# ECU_Dummy.net
KiCad netlist of a schematic drawn in Altium Designer
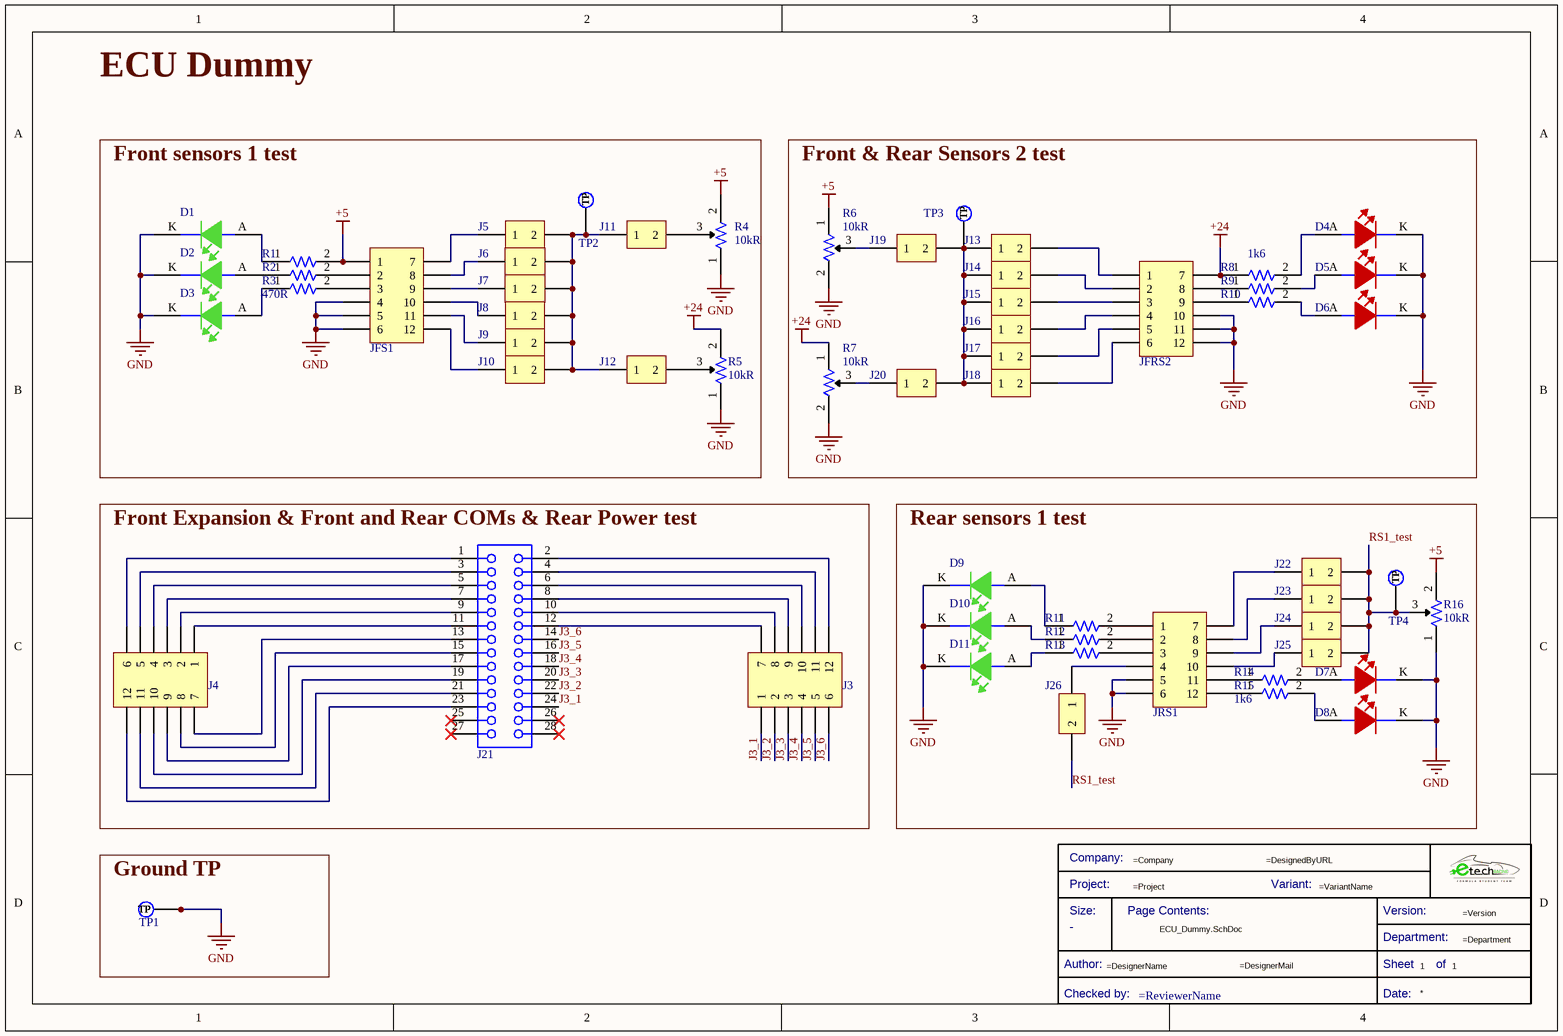
[diagram p0: ECU_Dummy.SchDoc]

(export (version "E")
  (design (tool "Eeschema 10.0.6"))
  (components
    (comp (ref "*")
      (value "Title Block_template")
      (description "Standard Title Block")
      (fields
        (field (name "SIZE") "-")
        (field (name ".CREATOR") "GP")
        (field (name ".PCBCHECK") "GP")
        (field (name ".SCHCHECK") "GP")
      )
      (libsource (lib "e-Tech_Racing") (part "Title Block_template"))
    )
    (comp (ref "D1")
      (value "150080GS75000")
      (footprint "LED_0805_WE")
      (description "Led, Green, 520 Nm, 3.2 V, 30 Ma, 450 Mcd Rohs Compliant: Yes")
      (fields (field (name ".CREATOR") "GP"))
      (libsource (lib "Semiconductor") (part "LEDGS-0805-450"))
    )
    (comp (ref "D2")
      (value "150080GS75000")
      (footprint "LED_0805_WE")
      (description "Led, Green, 520 Nm, 3.2 V, 30 Ma, 450 Mcd Rohs Compliant: Yes")
      (fields (field (name ".CREATOR") "GP"))
      (libsource (lib "Semiconductor") (part "LEDGS-0805-450"))
    )
    (comp (ref "D3")
      (value "150080GS75000")
      (footprint "LED_0805_WE")
      (description "Led, Green, 520 Nm, 3.2 V, 30 Ma, 450 Mcd Rohs Compliant: Yes")
      (fields (field (name ".CREATOR") "GP"))
      (libsource (lib "Semiconductor") (part "LEDGS-0805-450"))
    )
    (comp (ref "D4")
      (value "150080RS75000")
      (footprint "LED_0805_WE")
      (description "0805(H=0.8mm) 红色 高亮 λD=625nm VF=2V IF=30mA PD=72mW")
      (fields (field (name ".CREATOR") "DR"))
      (libsource (lib "Semiconductor") (part "LEDRS-0805-150"))
    )
    (comp (ref "D5")
      (value "150080RS75000")
      (footprint "LED_0805_WE")
      (description "0805(H=0.8mm) 红色 高亮 λD=625nm VF=2V IF=30mA PD=72mW")
      (fields (field (name ".CREATOR") "DR"))
      (libsource (lib "Semiconductor") (part "LEDRS-0805-150"))
    )
    (comp (ref "D6")
      (value "150080RS75000")
      (footprint "LED_0805_WE")
      (description "0805(H=0.8mm) 红色 高亮 λD=625nm VF=2V IF=30mA PD=72mW")
      (fields (field (name ".CREATOR") "DR"))
      (libsource (lib "Semiconductor") (part "LEDRS-0805-150"))
    )
    (comp (ref "D7")
      (value "150080RS75000")
      (footprint "LED_0805_WE")
      (description "0805(H=0.8mm) 红色 高亮 λD=625nm VF=2V IF=30mA PD=72mW")
      (fields (field (name ".CREATOR") "DR"))
      (libsource (lib "Semiconductor") (part "LEDRS-0805-150"))
    )
    (comp (ref "D8")
      (value "150080RS75000")
      (footprint "LED_0805_WE")
      (description "0805(H=0.8mm) 红色 高亮 λD=625nm VF=2V IF=30mA PD=72mW")
      (fields (field (name ".CREATOR") "DR"))
      (libsource (lib "Semiconductor") (part "LEDRS-0805-150"))
    )
    (comp (ref "D9")
      (value "150080GS75000")
      (footprint "LED_0805_WE")
      (description "Led, Green, 520 Nm, 3.2 V, 30 Ma, 450 Mcd Rohs Compliant: Yes")
      (fields (field (name ".CREATOR") "GP"))
      (libsource (lib "Semiconductor") (part "LEDGS-0805-450"))
    )
    (comp (ref "D10")
      (value "150080GS75000")
      (footprint "LED_0805_WE")
      (description "Led, Green, 520 Nm, 3.2 V, 30 Ma, 450 Mcd Rohs Compliant: Yes")
      (fields (field (name ".CREATOR") "GP"))
      (libsource (lib "Semiconductor") (part "LEDGS-0805-450"))
    )
    (comp (ref "D11")
      (value "150080GS75000")
      (footprint "LED_0805_WE")
      (description "Led, Green, 520 Nm, 3.2 V, 30 Ma, 450 Mcd Rohs Compliant: Yes")
      (fields (field (name ".CREATOR") "GP"))
      (libsource (lib "Semiconductor") (part "LEDGS-0805-450"))
    )
    (comp (ref "J3")
      (value "1053101112")
      (footprint "J_NanoFit_2x6_V")
      (libsource (lib "Electromechanical") (part "J_NanoFit_2x6_V"))
    )
    (comp (ref "J4")
      (value "1053101112")
      (footprint "J_NanoFit_2x6_V")
      (libsource (lib "") (part "J_NanoFit_2x6_V_1"))
    )
    (comp (ref "J5")
      (value "2 Pin Header")
      (footprint "J_Pinheader_1x2")
      (libsource (lib "Electromechanical") (part "J_Jumper_H"))
    )
    (comp (ref "J6")
      (value "2 Pin Header")
      (footprint "J_Pinheader_1x2")
      (libsource (lib "") (part "J_Jumper_H_2"))
    )
    (comp (ref "J7")
      (value "2 Pin Header")
      (footprint "J_Pinheader_1x2")
      (libsource (lib "") (part "J_Jumper_H_2"))
    )
    (comp (ref "J8")
      (value "2 Pin Header")
      (footprint "J_Pinheader_1x2")
      (libsource (lib "Electromechanical") (part "J_Jumper_H"))
    )
    (comp (ref "J9")
      (value "2 Pin Header")
      (footprint "J_Pinheader_1x2")
      (libsource (lib "Electromechanical") (part "J_Jumper_H"))
    )
    (comp (ref "J10")
      (value "2 Pin Header")
      (footprint "J_Pinheader_1x2")
      (libsource (lib "Electromechanical") (part "J_Jumper_H"))
    )
    (comp (ref "J11")
      (value "2 Pin Header")
      (footprint "J_Pinheader_1x2")
      (libsource (lib "Electromechanical") (part "J_Jumper_H"))
    )
    (comp (ref "J12")
      (value "2 Pin Header")
      (footprint "J_Pinheader_1x2")
      (libsource (lib "Electromechanical") (part "J_Jumper_H"))
    )
    (comp (ref "J13")
      (value "2 Pin Header")
      (footprint "J_Pinheader_1x2")
      (libsource (lib "Electromechanical") (part "J_Jumper_H"))
    )
    (comp (ref "J14")
      (value "2 Pin Header")
      (footprint "J_Pinheader_1x2")
      (libsource (lib "Electromechanical") (part "J_Jumper_H"))
    )
    (comp (ref "J15")
      (value "2 Pin Header")
      (footprint "J_Pinheader_1x2")
      (libsource (lib "Electromechanical") (part "J_Jumper_H"))
    )
    (comp (ref "J16")
      (value "2 Pin Header")
      (footprint "J_Pinheader_1x2")
      (libsource (lib "Electromechanical") (part "J_Jumper_H"))
    )
    (comp (ref "J17")
      (value "2 Pin Header")
      (footprint "J_Pinheader_1x2")
      (libsource (lib "Electromechanical") (part "J_Jumper_H"))
    )
    (comp (ref "J18")
      (value "2 Pin Header")
      (footprint "J_Pinheader_1x2")
      (libsource (lib "Electromechanical") (part "J_Jumper_H"))
    )
    (comp (ref "J19")
      (value "2 Pin Header")
      (footprint "J_Pinheader_1x2")
      (libsource (lib "Electromechanical") (part "J_Jumper_H"))
    )
    (comp (ref "J20")
      (value "2 Pin Header")
      (footprint "J_Pinheader_1x2")
      (libsource (lib "Electromechanical") (part "J_Jumper_H"))
    )
    (comp (ref "J21")
      (value "61002821821")
      (footprint "61002821821")
      (description "WR-PHD Socket Header, SMT, Vertical, pitch 2.54mm, 2 Row, 28P")
      (fields (field (name "MANUFACTURER") "Wurth Elektronik"))
      (libsource (lib "Electromechanical") (part "61002821821"))
    )
    (comp (ref "J22")
      (value "2 Pin Header")
      (footprint "J_Pinheader_1x2")
      (libsource (lib "Electromechanical") (part "J_Jumper_H"))
    )
    (comp (ref "J23")
      (value "2 Pin Header")
      (footprint "J_Pinheader_1x2")
      (libsource (lib "Electromechanical") (part "J_Jumper_H"))
    )
    (comp (ref "J24")
      (value "2 Pin Header")
      (footprint "J_Pinheader_1x2")
      (libsource (lib "Electromechanical") (part "J_Jumper_H"))
    )
    (comp (ref "J25")
      (value "2 Pin Header")
      (footprint "J_Pinheader_1x2")
      (libsource (lib "Electromechanical") (part "J_Jumper_H"))
    )
    (comp (ref "J26")
      (value "2 Pin Header")
      (footprint "J_Pinheader_1x2")
      (libsource (lib "") (part "J_Jumper_H_1"))
    )
    (comp (ref "JFRS2")
      (value "1053101112")
      (footprint "J_NanoFit_2x6_V")
      (libsource (lib "") (part "J_NanoFit_2x6_V_2"))
    )
    (comp (ref "JFS1")
      (value "1053101112")
      (footprint "J_NanoFit_2x6_V")
      (libsource (lib "") (part "J_NanoFit_2x6_V_2"))
    )
    (comp (ref "JRS1")
      (value "1053101112")
      (footprint "J_NanoFit_2x6_V")
      (libsource (lib "") (part "J_NanoFit_2x6_V_2"))
    )
    (comp (ref "R1")
      (value "CR0805-FX-4700GLF")
      (footprint "R0805FTK")
      (description "Res Thick Film 0805 470 Ohm 1% 1/8W ±100ppm/°C Molded SMD SMD Paper Tape on Plastic Reel")
      (fields (field (name "TOLERANCE") "1%") (field (name ".CREATOR") "DR"))
      (libsource (lib "Passives") (part "R470-0805FTK"))
    )
    (comp (ref "R2")
      (value "CR0805-FX-4700GLF")
      (footprint "R0805FTK")
      (description "Res Thick Film 0805 470 Ohm 1% 1/8W ±100ppm/°C Molded SMD SMD Paper Tape on Plastic Reel")
      (fields (field (name "TOLERANCE") "1%") (field (name ".CREATOR") "DR"))
      (libsource (lib "Passives") (part "R470-0805FTK"))
    )
    (comp (ref "R3")
      (value "CR0805-FX-4700GLF")
      (footprint "R0805FTK")
      (description "Res Thick Film 0805 470 Ohm 1% 1/8W ±100ppm/°C Molded SMD SMD Paper Tape on Plastic Reel")
      (fields (field (name "TOLERANCE") "1%") (field (name ".CREATOR") "DR"))
      (libsource (lib "Passives") (part "R470-0805FTK"))
    )
    (comp (ref "R4")
      (value "3296W-1-103LF")
      (footprint "R10k-VTR")
      (description "Trimmer, Cermet, Rest 10 Kilohms, PCB, 25 Turns, Pwr-Rtg 0.5W, 3296 Series")
      (fields
        (field (name "MANUFACTURER") "Bourns")
        (field (name "TOLERANCE") "10%")
        (field (name "RESISTANCE") "10kR")
        (field (name ".CREATOR") "DO")
      )
      (libsource (lib "Passives") (part "R10k-VTR"))
    )
    (comp (ref "R5")
      (value "3296W-1-103LF")
      (footprint "R10k-VTR")
      (description "Trimmer, Cermet, Rest 10 Kilohms, PCB, 25 Turns, Pwr-Rtg 0.5W, 3296 Series")
      (fields
        (field (name "MANUFACTURER") "Bourns")
        (field (name "TOLERANCE") "10%")
        (field (name "RESISTANCE") "10kR")
        (field (name ".CREATOR") "DO")
      )
      (libsource (lib "Passives") (part "R10k-VTR"))
    )
    (comp (ref "R6")
      (value "3296W-1-103LF")
      (footprint "R10k-VTR")
      (description "Trimmer, Cermet, Rest 10 Kilohms, PCB, 25 Turns, Pwr-Rtg 0.5W, 3296 Series")
      (fields
        (field (name "MANUFACTURER") "Bourns")
        (field (name "TOLERANCE") "10%")
        (field (name "RESISTANCE") "10kR")
        (field (name ".CREATOR") "DO")
      )
      (libsource (lib "Passives") (part "R10k-VTR"))
    )
    (comp (ref "R7")
      (value "3296W-1-103LF")
      (footprint "R10k-VTR")
      (description "Trimmer, Cermet, Rest 10 Kilohms, PCB, 25 Turns, Pwr-Rtg 0.5W, 3296 Series")
      (fields
        (field (name "MANUFACTURER") "Bourns")
        (field (name "TOLERANCE") "10%")
        (field (name "RESISTANCE") "10kR")
        (field (name ".CREATOR") "DO")
      )
      (libsource (lib "Passives") (part "R10k-VTR"))
    )
    (comp (ref "R8")
      (value "CR1206-FX-2201ELF")
      (footprint "R1206FTK-W")
      (description "Res Thick Film 1206 2.2K Ohm 1% 1/4W ±100ppm/°C Molded SMD SMD Paper Tape on Plastic Reel")
      (fields (field (name "TOLERANCE") "1%") (field (name ".CREATOR") "AC"))
      (libsource (lib "Passives") (part "R2.2K-1206FTK"))
    )
    (comp (ref "R9")
      (value "CR1206-FX-2201ELF")
      (footprint "R1206FTK-W")
      (description "Res Thick Film 1206 2.2K Ohm 1% 1/4W ±100ppm/°C Molded SMD SMD Paper Tape on Plastic Reel")
      (fields (field (name "TOLERANCE") "1%") (field (name ".CREATOR") "AC"))
      (libsource (lib "Passives") (part "R2.2K-1206FTK"))
    )
    (comp (ref "R10")
      (value "CR1206-FX-2201ELF")
      (footprint "R1206FTK-W")
      (description "Res Thick Film 1206 2.2K Ohm 1% 1/4W ±100ppm/°C Molded SMD SMD Paper Tape on Plastic Reel")
      (fields (field (name "TOLERANCE") "1%") (field (name ".CREATOR") "AC"))
      (libsource (lib "Passives") (part "R2.2K-1206FTK"))
    )
    (comp (ref "R11")
      (value "CR0805-FX-4700GLF")
      (footprint "R0805FTK")
      (description "Res Thick Film 0805 470 Ohm 1% 1/8W ±100ppm/°C Molded SMD SMD Paper Tape on Plastic Reel")
      (fields (field (name "TOLERANCE") "1%") (field (name ".CREATOR") "DR"))
      (libsource (lib "Passives") (part "R470-0805FTK"))
    )
    (comp (ref "R12")
      (value "CR0805-FX-4700GLF")
      (footprint "R0805FTK")
      (description "Res Thick Film 0805 470 Ohm 1% 1/8W ±100ppm/°C Molded SMD SMD Paper Tape on Plastic Reel")
      (fields (field (name "TOLERANCE") "1%") (field (name ".CREATOR") "DR"))
      (libsource (lib "Passives") (part "R470-0805FTK"))
    )
    (comp (ref "R13")
      (value "CR0805-FX-4700GLF")
      (footprint "R0805FTK")
      (description "Res Thick Film 0805 470 Ohm 1% 1/8W ±100ppm/°C Molded SMD SMD Paper Tape on Plastic Reel")
      (fields (field (name "TOLERANCE") "1%") (field (name ".CREATOR") "DR"))
      (libsource (lib "Passives") (part "R470-0805FTK"))
    )
    (comp (ref "R14")
      (value "CR1206-FX-2201ELF")
      (footprint "R1206FTK-W")
      (description "Res Thick Film 1206 2.2K Ohm 1% 1/4W ±100ppm/°C Molded SMD SMD Paper Tape on Plastic Reel")
      (fields (field (name "TOLERANCE") "1%") (field (name ".CREATOR") "AC"))
      (libsource (lib "Passives") (part "R2.2K-1206FTK"))
    )
    (comp (ref "R15")
      (value "CR1206-FX-2201ELF")
      (footprint "R1206FTK-W")
      (description "Res Thick Film 1206 2.2K Ohm 1% 1/4W ±100ppm/°C Molded SMD SMD Paper Tape on Plastic Reel")
      (fields (field (name "TOLERANCE") "1%") (field (name ".CREATOR") "AC"))
      (libsource (lib "Passives") (part "R2.2K-1206FTK"))
    )
    (comp (ref "R16")
      (value "3296W-1-103LF")
      (footprint "R10k-VTR")
      (description "Trimmer, Cermet, Rest 10 Kilohms, PCB, 25 Turns, Pwr-Rtg 0.5W, 3296 Series")
      (fields
        (field (name "MANUFACTURER") "Bourns")
        (field (name "TOLERANCE") "10%")
        (field (name "RESISTANCE") "10kR")
        (field (name ".CREATOR") "DO")
      )
      (libsource (lib "Passives") (part "R10k-VTR"))
    )
    (comp (ref "TP1")
      (value "Test Point")
      (footprint "TESTPOINT_WIDE")
      (description "TestPoint 5x5mm")
      (libsource (lib "e-Tech_Racing") (part "TestPoint_Wide"))
    )
    (comp (ref "TP2")
      (value "TestPoint")
      (footprint "TestPoint")
      (description "Test Point 1x1 mm")
      (fields (field (name ".CREATOR") "GP") (field (name ".PCBCHECK") "GP") (field (name ".SCHCHECK") "GP"))
      (libsource (lib "e-Tech_Racing") (part "TestPoint"))
    )
    (comp (ref "TP3")
      (value "TestPoint")
      (footprint "TestPoint")
      (description "Test Point 1x1 mm")
      (fields (field (name ".CREATOR") "GP") (field (name ".PCBCHECK") "GP") (field (name ".SCHCHECK") "GP"))
      (libsource (lib "e-Tech_Racing") (part "TestPoint"))
    )
    (comp (ref "TP4")
      (value "TestPoint")
      (footprint "TestPoint")
      (description "Test Point 1x1 mm")
      (fields (field (name ".CREATOR") "GP") (field (name ".PCBCHECK") "GP") (field (name ".SCHCHECK") "GP"))
      (libsource (lib "e-Tech_Racing") (part "TestPoint"))
    )
  )
  (nets
    (net (code "1") (name "+5") (class "Default")
      (node (ref "JFS1") (pin "1") (pinfunction "1_1") (pintype "passive"))
      (node (ref "R1") (pin "2") (pinfunction "2_2") (pintype "passive"))
      (node (ref "R16") (pin "2") (pinfunction "2_2") (pintype "passive"))
      (node (ref "R4") (pin "2") (pinfunction "2_2") (pintype "passive"))
      (node (ref "R6") (pin "1") (pinfunction "2_1") (pintype "passive"))
    )
    (net (code "2") (name "+24") (class "Default")
      (node (ref "JFRS2") (pin "7") (pinfunction "7_7") (pintype "passive"))
      (node (ref "R5") (pin "2") (pinfunction "2_2") (pintype "passive"))
      (node (ref "R7") (pin "1") (pinfunction "2_1") (pintype "passive"))
      (node (ref "R8") (pin "1") (pinfunction "1_1") (pintype "passive"))
    )
    (net (code "3") (name "/J3_1") (class "Default")
      (node (ref "J21") (pin "24") (pinfunction "24_24") (pintype "passive"))
      (node (ref "J3") (pin "1") (pinfunction "1_1") (pintype "passive"))
    )
    (net (code "4") (name "/J3_2") (class "Default")
      (node (ref "J21") (pin "22") (pinfunction "22_22") (pintype "passive"))
      (node (ref "J3") (pin "2") (pinfunction "2_2") (pintype "passive"))
    )
    (net (code "5") (name "/J3_3") (class "Default")
      (node (ref "J21") (pin "20") (pinfunction "20_20") (pintype "passive"))
      (node (ref "J3") (pin "3") (pinfunction "3_3") (pintype "passive"))
    )
    (net (code "6") (name "/J3_4") (class "Default")
      (node (ref "J21") (pin "18") (pinfunction "18_18") (pintype "passive"))
      (node (ref "J3") (pin "4") (pinfunction "4_4") (pintype "passive"))
    )
    (net (code "7") (name "/J3_5") (class "Default")
      (node (ref "J21") (pin "16") (pinfunction "16_16") (pintype "passive"))
      (node (ref "J3") (pin "5") (pinfunction "5_5") (pintype "passive"))
    )
    (net (code "8") (name "/J3_6") (class "Default")
      (node (ref "J21") (pin "14") (pinfunction "14_14") (pintype "passive"))
      (node (ref "J3") (pin "6") (pinfunction "6_6") (pintype "passive"))
    )
    (net (code "9") (name "/RS1_test") (class "Default")
      (node (ref "J22") (pin "2") (pinfunction "2_2") (pintype "passive"))
      (node (ref "J23") (pin "2") (pinfunction "2_2") (pintype "passive"))
      (node (ref "J24") (pin "2") (pinfunction "2_2") (pintype "passive"))
      (node (ref "J25") (pin "2") (pinfunction "2_2") (pintype "passive"))
      (node (ref "J26") (pin "2") (pinfunction "2_2") (pintype "passive"))
      (node (ref "R16") (pin "3") (pinfunction "3_3") (pintype "passive"))
      (node (ref "TP4") (pin "1") (pinfunction "TP_1") (pintype "passive"))
    )
    (net (code "10") (name "GND") (class "Default")
      (node (ref "D1") (pin "K") (pinfunction "K_K") (pintype "passive"))
      (node (ref "D10") (pin "K") (pinfunction "K_K") (pintype "passive"))
      (node (ref "D11") (pin "K") (pinfunction "K_K") (pintype "passive"))
      (node (ref "D2") (pin "K") (pinfunction "K_K") (pintype "passive"))
      (node (ref "D3") (pin "K") (pinfunction "K_K") (pintype "passive"))
      (node (ref "D4") (pin "K") (pinfunction "K_K") (pintype "passive"))
      (node (ref "D5") (pin "K") (pinfunction "K_K") (pintype "passive"))
      (node (ref "D6") (pin "K") (pinfunction "K_K") (pintype "passive"))
      (node (ref "D7") (pin "K") (pinfunction "K_K") (pintype "passive"))
      (node (ref "D8") (pin "K") (pinfunction "K_K") (pintype "passive"))
      (node (ref "D9") (pin "K") (pinfunction "K_K") (pintype "passive"))
      (node (ref "JFRS2") (pin "10") (pinfunction "10_10") (pintype "passive"))
      (node (ref "JFRS2") (pin "11") (pinfunction "11_11") (pintype "passive"))
      (node (ref "JFRS2") (pin "12") (pinfunction "12_12") (pintype "passive"))
      (node (ref "JFS1") (pin "4") (pinfunction "4_4") (pintype "passive"))
      (node (ref "JFS1") (pin "5") (pinfunction "5_5") (pintype "passive"))
      (node (ref "JFS1") (pin "6") (pinfunction "6_6") (pintype "passive"))
      (node (ref "JRS1") (pin "5") (pinfunction "5_5") (pintype "passive"))
      (node (ref "JRS1") (pin "6") (pinfunction "6_6") (pintype "passive"))
      (node (ref "R16") (pin "1") (pinfunction "2_1") (pintype "passive"))
      (node (ref "R4") (pin "1") (pinfunction "2_1") (pintype "passive"))
      (node (ref "R5") (pin "1") (pinfunction "2_1") (pintype "passive"))
      (node (ref "R6") (pin "2") (pinfunction "2_2") (pintype "passive"))
      (node (ref "R7") (pin "2") (pinfunction "2_2") (pintype "passive"))
      (node (ref "TP1") (pin "1") (pinfunction "TP_1") (pintype "passive"))
    )
    (net (code "11") (name "Net-(D1-PadA)") (class "Default")
      (node (ref "D1") (pin "A") (pinfunction "A_A") (pintype "passive"))
      (node (ref "R1") (pin "1") (pinfunction "1_1") (pintype "passive"))
    )
    (net (code "12") (name "Net-(D2-PadA)") (class "Default")
      (node (ref "D2") (pin "A") (pinfunction "A_A") (pintype "passive"))
      (node (ref "R2") (pin "1") (pinfunction "1_1") (pintype "passive"))
    )
    (net (code "13") (name "Net-(D3-PadA)") (class "Default")
      (node (ref "D3") (pin "A") (pinfunction "A_A") (pintype "passive"))
      (node (ref "R3") (pin "1") (pinfunction "1_1") (pintype "passive"))
    )
    (net (code "14") (name "Net-(D4-PadA)") (class "Default")
      (node (ref "D4") (pin "A") (pinfunction "A_A") (pintype "passive"))
      (node (ref "R8") (pin "2") (pinfunction "2_2") (pintype "passive"))
    )
    (net (code "15") (name "Net-(D5-PadA)") (class "Default")
      (node (ref "D5") (pin "A") (pinfunction "A_A") (pintype "passive"))
      (node (ref "R9") (pin "2") (pinfunction "2_2") (pintype "passive"))
    )
    (net (code "16") (name "Net-(D6-PadA)") (class "Default")
      (node (ref "D6") (pin "A") (pinfunction "A_A") (pintype "passive"))
      (node (ref "R10") (pin "2") (pinfunction "2_2") (pintype "passive"))
    )
    (net (code "17") (name "Net-(D7-PadA)") (class "Default")
      (node (ref "D7") (pin "A") (pinfunction "A_A") (pintype "passive"))
      (node (ref "R14") (pin "2") (pinfunction "2_2") (pintype "passive"))
    )
    (net (code "18") (name "Net-(D8-PadA)") (class "Default")
      (node (ref "D8") (pin "A") (pinfunction "A_A") (pintype "passive"))
      (node (ref "R15") (pin "2") (pinfunction "2_2") (pintype "passive"))
    )
    (net (code "19") (name "Net-(D9-PadA)") (class "Default")
      (node (ref "D9") (pin "A") (pinfunction "A_A") (pintype "passive"))
      (node (ref "R11") (pin "1") (pinfunction "1_1") (pintype "passive"))
    )
    (net (code "20") (name "Net-(D10-PadA)") (class "Default")
      (node (ref "D10") (pin "A") (pinfunction "A_A") (pintype "passive"))
      (node (ref "R12") (pin "1") (pinfunction "1_1") (pintype "passive"))
    )
    (net (code "21") (name "Net-(D11-PadA)") (class "Default")
      (node (ref "D11") (pin "A") (pinfunction "A_A") (pintype "passive"))
      (node (ref "R13") (pin "1") (pinfunction "1_1") (pintype "passive"))
    )
    (net (code "22") (name "Net-(J5-Pad1)") (class "Default")
      (node (ref "J5") (pin "1") (pinfunction "1_1") (pintype "passive"))
      (node (ref "JFS1") (pin "7") (pinfunction "7_7") (pintype "passive"))
    )
    (net (code "23") (name "Net-(J6-Pad1)") (class "Default")
      (node (ref "J6") (pin "1") (pinfunction "1_1") (pintype "passive"))
      (node (ref "JFS1") (pin "8") (pinfunction "8_8") (pintype "passive"))
    )
    (net (code "24") (name "Net-(J7-Pad1)") (class "Default")
      (node (ref "J7") (pin "1") (pinfunction "1_1") (pintype "passive"))
      (node (ref "JFS1") (pin "9") (pinfunction "9_9") (pintype "passive"))
    )
    (net (code "25") (name "Net-(J8-Pad1)") (class "Default")
      (node (ref "J8") (pin "1") (pinfunction "1_1") (pintype "passive"))
      (node (ref "JFS1") (pin "10") (pinfunction "10_10") (pintype "passive"))
    )
    (net (code "26") (name "Net-(J9-Pad1)") (class "Default")
      (node (ref "J9") (pin "1") (pinfunction "1_1") (pintype "passive"))
      (node (ref "JFS1") (pin "11") (pinfunction "11_11") (pintype "passive"))
    )
    (net (code "27") (name "Net-(J10-Pad1)") (class "Default")
      (node (ref "J10") (pin "1") (pinfunction "1_1") (pintype "passive"))
      (node (ref "JFS1") (pin "12") (pinfunction "12_12") (pintype "passive"))
    )
    (net (code "28") (name "Net-(J11-Pad2)") (class "Default")
      (node (ref "J11") (pin "2") (pinfunction "2_2") (pintype "passive"))
      (node (ref "R4") (pin "3") (pinfunction "3_3") (pintype "passive"))
    )
    (net (code "29") (name "Net-(J12-Pad2)") (class "Default")
      (node (ref "J12") (pin "2") (pinfunction "2_2") (pintype "passive"))
      (node (ref "R5") (pin "3") (pinfunction "3_3") (pintype "passive"))
    )
    (net (code "30") (name "Net-(J13-Pad2)") (class "Default")
      (node (ref "J13") (pin "2") (pinfunction "2_2") (pintype "passive"))
      (node (ref "JFRS2") (pin "1") (pinfunction "1_1") (pintype "passive"))
    )
    (net (code "31") (name "Net-(J14-Pad2)") (class "Default")
      (node (ref "J14") (pin "2") (pinfunction "2_2") (pintype "passive"))
      (node (ref "JFRS2") (pin "2") (pinfunction "2_2") (pintype "passive"))
    )
    (net (code "32") (name "Net-(J15-Pad2)") (class "Default")
      (node (ref "J15") (pin "2") (pinfunction "2_2") (pintype "passive"))
      (node (ref "JFRS2") (pin "3") (pinfunction "3_3") (pintype "passive"))
    )
    (net (code "33") (name "Net-(J16-Pad2)") (class "Default")
      (node (ref "J16") (pin "2") (pinfunction "2_2") (pintype "passive"))
      (node (ref "JFRS2") (pin "4") (pinfunction "4_4") (pintype "passive"))
    )
    (net (code "34") (name "Net-(J17-Pad2)") (class "Default")
      (node (ref "J17") (pin "2") (pinfunction "2_2") (pintype "passive"))
      (node (ref "JFRS2") (pin "5") (pinfunction "5_5") (pintype "passive"))
    )
    (net (code "35") (name "Net-(J18-Pad2)") (class "Default")
      (node (ref "J18") (pin "2") (pinfunction "2_2") (pintype "passive"))
      (node (ref "JFRS2") (pin "6") (pinfunction "6_6") (pintype "passive"))
    )
    (net (code "36") (name "Net-(J19-Pad1)") (class "Default")
      (node (ref "J19") (pin "1") (pinfunction "1_1") (pintype "passive"))
      (node (ref "R6") (pin "3") (pinfunction "3_3") (pintype "passive"))
    )
    (net (code "37") (name "Net-(J20-Pad1)") (class "Default")
      (node (ref "J20") (pin "1") (pinfunction "1_1") (pintype "passive"))
      (node (ref "R7") (pin "3") (pinfunction "3_3") (pintype "passive"))
    )
    (net (code "38") (name "Net-(J21-Pad1)") (class "Default")
      (node (ref "J21") (pin "1") (pinfunction "1_1") (pintype "passive"))
      (node (ref "J4") (pin "6") (pinfunction "6_6") (pintype "passive"))
    )
    (net (code "39") (name "Net-(J21-Pad2)") (class "Default")
      (node (ref "J21") (pin "2") (pinfunction "2_2") (pintype "passive"))
      (node (ref "J3") (pin "12") (pinfunction "12_12") (pintype "passive"))
    )
    (net (code "40") (name "Net-(J21-Pad3)") (class "Default")
      (node (ref "J21") (pin "3") (pinfunction "3_3") (pintype "passive"))
      (node (ref "J4") (pin "5") (pinfunction "5_5") (pintype "passive"))
    )
    (net (code "41") (name "Net-(J21-Pad4)") (class "Default")
      (node (ref "J21") (pin "4") (pinfunction "4_4") (pintype "passive"))
      (node (ref "J3") (pin "11") (pinfunction "11_11") (pintype "passive"))
    )
    (net (code "42") (name "Net-(J21-Pad5)") (class "Default")
      (node (ref "J21") (pin "5") (pinfunction "5_5") (pintype "passive"))
      (node (ref "J4") (pin "4") (pinfunction "4_4") (pintype "passive"))
    )
    (net (code "43") (name "Net-(J21-Pad6)") (class "Default")
      (node (ref "J21") (pin "6") (pinfunction "6_6") (pintype "passive"))
      (node (ref "J3") (pin "10") (pinfunction "10_10") (pintype "passive"))
    )
    (net (code "44") (name "Net-(J21-Pad7)") (class "Default")
      (node (ref "J21") (pin "7") (pinfunction "7_7") (pintype "passive"))
      (node (ref "J4") (pin "3") (pinfunction "3_3") (pintype "passive"))
    )
    (net (code "45") (name "Net-(J21-Pad8)") (class "Default")
      (node (ref "J21") (pin "8") (pinfunction "8_8") (pintype "passive"))
      (node (ref "J3") (pin "9") (pinfunction "9_9") (pintype "passive"))
    )
    (net (code "46") (name "Net-(J21-Pad9)") (class "Default")
      (node (ref "J21") (pin "9") (pinfunction "9_9") (pintype "passive"))
      (node (ref "J4") (pin "2") (pinfunction "2_2") (pintype "passive"))
    )
    (net (code "47") (name "Net-(J21-Pad10)") (class "Default")
      (node (ref "J21") (pin "10") (pinfunction "10_10") (pintype "passive"))
      (node (ref "J3") (pin "8") (pinfunction "8_8") (pintype "passive"))
    )
    (net (code "48") (name "Net-(J21-Pad11)") (class "Default")
      (node (ref "J21") (pin "11") (pinfunction "11_11") (pintype "passive"))
      (node (ref "J4") (pin "1") (pinfunction "1_1") (pintype "passive"))
    )
    (net (code "49") (name "Net-(J21-Pad12)") (class "Default")
      (node (ref "J21") (pin "12") (pinfunction "12_12") (pintype "passive"))
      (node (ref "J3") (pin "7") (pinfunction "7_7") (pintype "passive"))
    )
    (net (code "50") (name "Net-(J21-Pad13)") (class "Default")
      (node (ref "J21") (pin "13") (pinfunction "13_13") (pintype "passive"))
      (node (ref "J4") (pin "7") (pinfunction "7_7") (pintype "passive"))
    )
    (net (code "51") (name "Net-(J21-Pad15)") (class "Default")
      (node (ref "J21") (pin "15") (pinfunction "15_15") (pintype "passive"))
      (node (ref "J4") (pin "8") (pinfunction "8_8") (pintype "passive"))
    )
    (net (code "52") (name "Net-(J21-Pad17)") (class "Default")
      (node (ref "J21") (pin "17") (pinfunction "17_17") (pintype "passive"))
      (node (ref "J4") (pin "9") (pinfunction "9_9") (pintype "passive"))
    )
    (net (code "53") (name "Net-(J21-Pad19)") (class "Default")
      (node (ref "J21") (pin "19") (pinfunction "19_19") (pintype "passive"))
      (node (ref "J4") (pin "10") (pinfunction "10_10") (pintype "passive"))
    )
    (net (code "54") (name "Net-(J21-Pad21)") (class "Default")
      (node (ref "J21") (pin "21") (pinfunction "21_21") (pintype "passive"))
      (node (ref "J4") (pin "11") (pinfunction "11_11") (pintype "passive"))
    )
    (net (code "55") (name "Net-(J21-Pad23)") (class "Default")
      (node (ref "J21") (pin "23") (pinfunction "23_23") (pintype "passive"))
      (node (ref "J4") (pin "12") (pinfunction "12_12") (pintype "passive"))
    )
    (net (code "56") (name "Net-(J22-Pad1)") (class "Default")
      (node (ref "J22") (pin "1") (pinfunction "1_1") (pintype "passive"))
      (node (ref "JRS1") (pin "7") (pinfunction "7_7") (pintype "passive"))
    )
    (net (code "57") (name "Net-(J23-Pad1)") (class "Default")
      (node (ref "J23") (pin "1") (pinfunction "1_1") (pintype "passive"))
      (node (ref "JRS1") (pin "8") (pinfunction "8_8") (pintype "passive"))
    )
    (net (code "58") (name "Net-(J24-Pad1)") (class "Default")
      (node (ref "J24") (pin "1") (pinfunction "1_1") (pintype "passive"))
      (node (ref "JRS1") (pin "9") (pinfunction "9_9") (pintype "passive"))
    )
    (net (code "59") (name "Net-(J25-Pad1)") (class "Default")
      (node (ref "J25") (pin "1") (pinfunction "1_1") (pintype "passive"))
      (node (ref "JRS1") (pin "10") (pinfunction "10_10") (pintype "passive"))
    )
    (net (code "60") (name "Net-(J26-Pad1)") (class "Default")
      (node (ref "J26") (pin "1") (pinfunction "1_1") (pintype "passive"))
      (node (ref "JRS1") (pin "4") (pinfunction "4_4") (pintype "passive"))
    )
    (net (code "61") (name "Net-(JFRS2-Pad8)") (class "Default")
      (node (ref "JFRS2") (pin "8") (pinfunction "8_8") (pintype "passive"))
      (node (ref "R9") (pin "1") (pinfunction "1_1") (pintype "passive"))
    )
    (net (code "62") (name "Net-(JFRS2-Pad9)") (class "Default")
      (node (ref "JFRS2") (pin "9") (pinfunction "9_9") (pintype "passive"))
      (node (ref "R10") (pin "1") (pinfunction "1_1") (pintype "passive"))
    )
    (net (code "63") (name "Net-(JFS1-Pad2)") (class "Default")
      (node (ref "JFS1") (pin "2") (pinfunction "2_2") (pintype "passive"))
      (node (ref "R2") (pin "2") (pinfunction "2_2") (pintype "passive"))
    )
    (net (code "64") (name "Net-(JFS1-Pad3)") (class "Default")
      (node (ref "JFS1") (pin "3") (pinfunction "3_3") (pintype "passive"))
      (node (ref "R3") (pin "2") (pinfunction "2_2") (pintype "passive"))
    )
    (net (code "65") (name "Net-(JRS1-Pad1)") (class "Default")
      (node (ref "JRS1") (pin "1") (pinfunction "1_1") (pintype "passive"))
      (node (ref "R11") (pin "2") (pinfunction "2_2") (pintype "passive"))
    )
    (net (code "66") (name "Net-(JRS1-Pad2)") (class "Default")
      (node (ref "JRS1") (pin "2") (pinfunction "2_2") (pintype "passive"))
      (node (ref "R12") (pin "2") (pinfunction "2_2") (pintype "passive"))
    )
    (net (code "67") (name "Net-(JRS1-Pad3)") (class "Default")
      (node (ref "JRS1") (pin "3") (pinfunction "3_3") (pintype "passive"))
      (node (ref "R13") (pin "2") (pinfunction "2_2") (pintype "passive"))
    )
    (net (code "68") (name "Net-(JRS1-Pad11)") (class "Default")
      (node (ref "JRS1") (pin "11") (pinfunction "11_11") (pintype "passive"))
      (node (ref "R14") (pin "1") (pinfunction "1_1") (pintype "passive"))
    )
    (net (code "69") (name "Net-(JRS1-Pad12)") (class "Default")
      (node (ref "JRS1") (pin "12") (pinfunction "12_12") (pintype "passive"))
      (node (ref "R15") (pin "1") (pinfunction "1_1") (pintype "passive"))
    )
    (net (code "70") (name "Net-(TP2-TP)") (class "Default")
      (node (ref "J10") (pin "2") (pinfunction "2_2") (pintype "passive"))
      (node (ref "J11") (pin "1") (pinfunction "1_1") (pintype "passive"))
      (node (ref "J12") (pin "1") (pinfunction "1_1") (pintype "passive"))
      (node (ref "J5") (pin "2") (pinfunction "2_2") (pintype "passive"))
      (node (ref "J6") (pin "2") (pinfunction "2_2") (pintype "passive"))
      (node (ref "J7") (pin "2") (pinfunction "2_2") (pintype "passive"))
      (node (ref "J8") (pin "2") (pinfunction "2_2") (pintype "passive"))
      (node (ref "J9") (pin "2") (pinfunction "2_2") (pintype "passive"))
      (node (ref "TP2") (pin "1") (pinfunction "TP_1") (pintype "passive"))
    )
    (net (code "71") (name "Net-(TP3-TP)") (class "Default")
      (node (ref "J13") (pin "1") (pinfunction "1_1") (pintype "passive"))
      (node (ref "J14") (pin "1") (pinfunction "1_1") (pintype "passive"))
      (node (ref "J15") (pin "1") (pinfunction "1_1") (pintype "passive"))
      (node (ref "J16") (pin "1") (pinfunction "1_1") (pintype "passive"))
      (node (ref "J17") (pin "1") (pinfunction "1_1") (pintype "passive"))
      (node (ref "J18") (pin "1") (pinfunction "1_1") (pintype "passive"))
      (node (ref "J19") (pin "2") (pinfunction "2_2") (pintype "passive"))
      (node (ref "J20") (pin "2") (pinfunction "2_2") (pintype "passive"))
      (node (ref "TP3") (pin "1") (pinfunction "TP_1") (pintype "passive"))
    )
    (net (code "72") (name "unconnected-(J21-Pad25)") (class "Default")
      (node (ref "J21") (pin "25") (pinfunction "25_25") (pintype "passive+no_connect"))
    )
    (net (code "73") (name "unconnected-(J21-Pad26)") (class "Default")
      (node (ref "J21") (pin "26") (pinfunction "26_26") (pintype "passive+no_connect"))
    )
    (net (code "74") (name "unconnected-(J21-Pad27)") (class "Default")
      (node (ref "J21") (pin "27") (pinfunction "27_27") (pintype "passive+no_connect"))
    )
    (net (code "75") (name "unconnected-(J21-Pad28)") (class "Default")
      (node (ref "J21") (pin "28") (pinfunction "28_28") (pintype "passive+no_connect"))
    )
  )
)
